# type5comparator.net
KiCad netlist of a schematic drawn in EAGLE
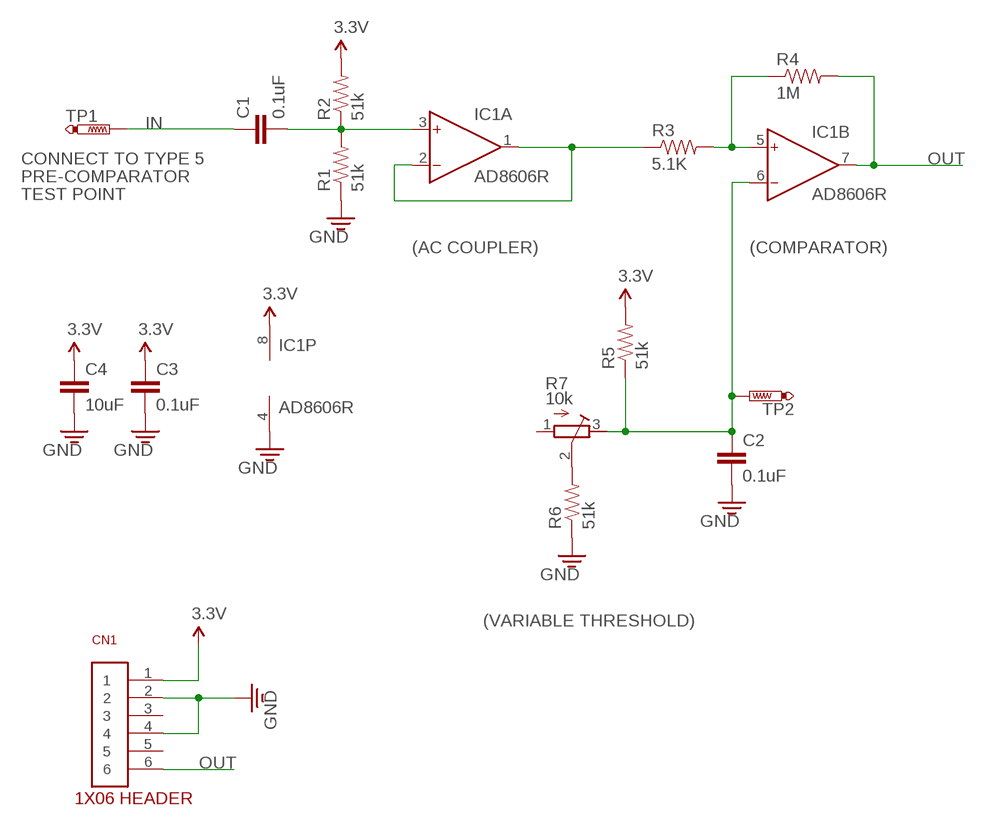
[diagram p0: schematic, sheet 1]

(export (version "E")
  (design (tool "Eeschema 10.0.6"))
  (components
    (comp (ref "C1")
      (value "0.1uF")
      (footprint "eagle-import:0603")
      (libsource (lib "eagle-import") (part "CAP0603"))
    )
    (comp (ref "C2")
      (value "0.1uF")
      (footprint "eagle-import:0603")
      (libsource (lib "eagle-import") (part "CAP0603"))
    )
    (comp (ref "C3")
      (value "0.1uF")
      (footprint "eagle-import:0603")
      (libsource (lib "eagle-import") (part "CAP0603"))
    )
    (comp (ref "C4")
      (value "10uF")
      (footprint "eagle-import:0603")
      (libsource (lib "eagle-import") (part "CAP0603"))
    )
    (comp (ref "CN1")
      (value "1X06")
      (footprint "eagle-import:1X06")
      (libsource (lib "eagle-import") (part "1X06"))
    )
    (comp (ref "IC1")
      (value "AD8606R")
      (footprint "eagle-import:SO8")
      (fields (field (name "MPN") "AD8607ARMZ-R2"))
      (libsource (lib "eagle-import") (part "AD8607R"))
    )
    (comp (ref "R1")
      (value "51k")
      (footprint "eagle-import:0603")
      (libsource (lib "eagle-import") (part "RESISTOR0603"))
    )
    (comp (ref "R2")
      (value "51k")
      (footprint "eagle-import:0603")
      (libsource (lib "eagle-import") (part "RESISTOR0603"))
    )
    (comp (ref "R3")
      (value "5.1K")
      (footprint "eagle-import:0603")
      (libsource (lib "eagle-import") (part "RESISTOR0603"))
    )
    (comp (ref "R4")
      (value "1M")
      (footprint "eagle-import:0603")
      (libsource (lib "eagle-import") (part "RESISTOR0603"))
    )
    (comp (ref "R5")
      (value "51k")
      (footprint "eagle-import:0603")
      (libsource (lib "eagle-import") (part "RESISTOR0603"))
    )
    (comp (ref "R6")
      (value "51k")
      (footprint "eagle-import:0603")
      (libsource (lib "eagle-import") (part "RESISTOR0603"))
    )
    (comp (ref "R7")
      (value "10k")
      (footprint "eagle-import:RTRIM3299W")
      (libsource (lib "eagle-import") (part "R-TRIMM3299W"))
    )
    (comp (ref "TP1")
      (value "PTR1PAD1-13")
      (footprint "eagle-import:P1-13")
      (libsource (lib "eagle-import") (part "PTR1PAD1-13"))
    )
    (comp (ref "TP2")
      (value "PTR1PAD1-13")
      (footprint "eagle-import:P1-13")
      (libsource (lib "eagle-import") (part "PTR1PAD1-13"))
    )
  )
  (nets
    (net (code "1") (name "/IN") (class "Default")
      (node (ref "C1") (pin "1") (pinfunction "1_1") (pintype "passive"))
      (node (ref "TP1") (pin "TP") (pinfunction "TP_TP") (pintype "input"))
    )
    (net (code "2") (name "/OUT") (class "Default")
      (node (ref "CN1") (pin "6") (pinfunction "6_6") (pintype "bidirectional"))
      (node (ref "IC1") (pin "7") (pinfunction "OUT_7") (pintype "output"))
      (node (ref "R4") (pin "2") (pinfunction "2_2") (pintype "passive"))
    )
    (net (code "3") (name "3.3V") (class "Default")
      (node (ref "C3") (pin "1") (pinfunction "1_1") (pintype "passive"))
      (node (ref "C4") (pin "1") (pinfunction "1_1") (pintype "passive"))
      (node (ref "CN1") (pin "1") (pinfunction "1_1") (pintype "bidirectional"))
      (node (ref "IC1") (pin "8") (pinfunction "V+_8") (pintype "power_in"))
      (node (ref "R2") (pin "2") (pinfunction "2_2") (pintype "passive"))
      (node (ref "R5") (pin "2") (pinfunction "2_2") (pintype "passive"))
    )
    (net (code "4") (name "GND") (class "Default")
      (node (ref "C2") (pin "2") (pinfunction "2_2") (pintype "passive"))
      (node (ref "C3") (pin "2") (pinfunction "2_2") (pintype "passive"))
      (node (ref "C4") (pin "2") (pinfunction "2_2") (pintype "passive"))
      (node (ref "CN1") (pin "2") (pinfunction "2_2") (pintype "bidirectional"))
      (node (ref "CN1") (pin "4") (pinfunction "4_4") (pintype "bidirectional"))
      (node (ref "IC1") (pin "4") (pinfunction "V-_4") (pintype "power_in"))
      (node (ref "R1") (pin "1") (pinfunction "1_1") (pintype "passive"))
      (node (ref "R6") (pin "1") (pinfunction "1_1") (pintype "passive"))
    )
    (net (code "5") (name "Net-(IC1A-IN+)") (class "Default")
      (node (ref "C1") (pin "2") (pinfunction "2_2") (pintype "passive"))
      (node (ref "IC1") (pin "3") (pinfunction "IN+_3") (pintype "input"))
      (node (ref "R1") (pin "2") (pinfunction "2_2") (pintype "passive"))
      (node (ref "R2") (pin "1") (pinfunction "1_1") (pintype "passive"))
    )
    (net (code "6") (name "Net-(IC1A-IN-)") (class "Default")
      (node (ref "IC1") (pin "1") (pinfunction "OUT_1") (pintype "output"))
      (node (ref "IC1") (pin "2") (pinfunction "IN-_2") (pintype "input"))
      (node (ref "R3") (pin "1") (pinfunction "1_1") (pintype "passive"))
    )
    (net (code "7") (name "Net-(IC1B-IN+)") (class "Default")
      (node (ref "IC1") (pin "5") (pinfunction "IN+_5") (pintype "input"))
      (node (ref "R3") (pin "2") (pinfunction "2_2") (pintype "passive"))
      (node (ref "R4") (pin "1") (pinfunction "1_1") (pintype "passive"))
    )
    (net (code "8") (name "Net-(IC1B-IN-)") (class "Default")
      (node (ref "C2") (pin "1") (pinfunction "1_1") (pintype "passive"))
      (node (ref "IC1") (pin "6") (pinfunction "IN-_6") (pintype "input"))
      (node (ref "R5") (pin "1") (pinfunction "1_1") (pintype "passive"))
      (node (ref "R7") (pin "3") (pinfunction "A_3") (pintype "passive"))
      (node (ref "TP2") (pin "TP") (pinfunction "TP_TP") (pintype "input"))
    )
    (net (code "9") (name "Net-(R7-S)") (class "Default")
      (node (ref "R6") (pin "2") (pinfunction "2_2") (pintype "passive"))
      (node (ref "R7") (pin "2") (pinfunction "S_2") (pintype "passive"))
    )
    (net (code "10") (name "unconnected-(CN1-Pad3)") (class "Default")
      (node (ref "CN1") (pin "3") (pinfunction "3_3") (pintype "bidirectional"))
    )
    (net (code "11") (name "unconnected-(CN1-Pad5)") (class "Default")
      (node (ref "CN1") (pin "5") (pinfunction "5_5") (pintype "bidirectional"))
    )
    (net (code "12") (name "unconnected-(R7-E-Pad1)") (class "Default")
      (node (ref "R7") (pin "1") (pinfunction "E_1") (pintype "passive"))
    )
  )
)
